# pidControllerRev8.net
KiCad netlist of a schematic drawn in EAGLE
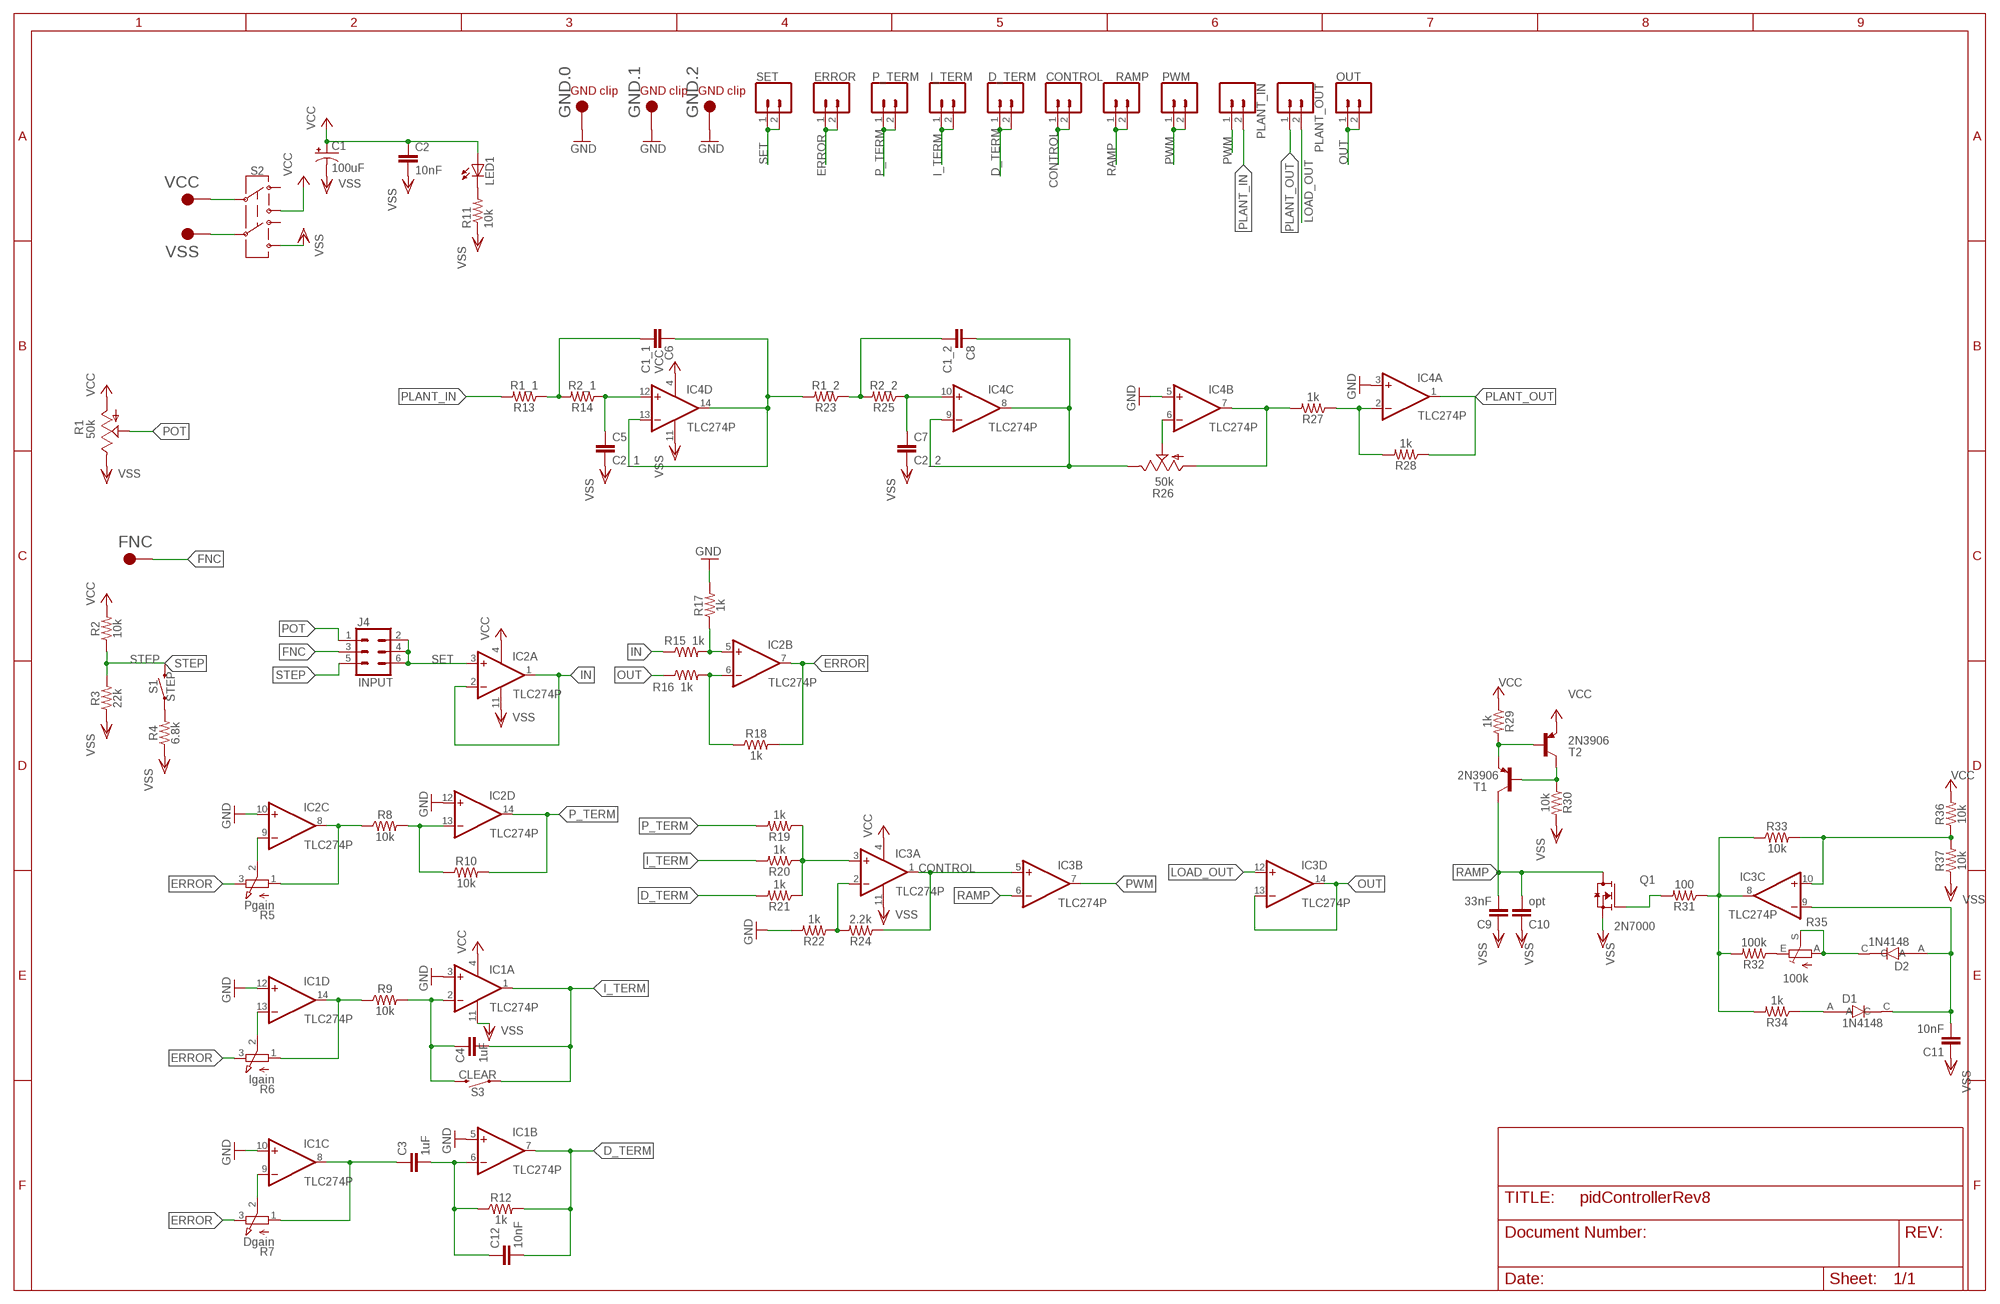
[diagram p0: schematic, sheet 1]

(export (version "E")
  (design (tool "Eeschema 10.0.6"))
  (components
    (comp (ref "C1")
      (value "100uF")
      (footprint "eagle-import:SANYO-OSCON_C")
      (libsource (lib "eagle-import") (part "CPOL-USSANYO_C"))
    )
    (comp (ref "C2")
      (value "10nF")
      (footprint "eagle-import:C1206")
      (libsource (lib "eagle-import") (part "C-EUC1206"))
    )
    (comp (ref "C3")
      (value "1uF")
      (footprint "eagle-import:C1206")
      (libsource (lib "eagle-import") (part "C-EUC1206"))
    )
    (comp (ref "C4")
      (value "1uF")
      (footprint "eagle-import:C1206")
      (libsource (lib "eagle-import") (part "C-EUC1206"))
    )
    (comp (ref "C5")
      (value "C2_1")
      (footprint "eagle-import:C1206")
      (libsource (lib "eagle-import") (part "C-EUC1206"))
    )
    (comp (ref "C6")
      (value "C1_1")
      (footprint "eagle-import:C1206")
      (libsource (lib "eagle-import") (part "C-EUC1206"))
    )
    (comp (ref "C7")
      (value "C2_2")
      (footprint "eagle-import:C1206")
      (libsource (lib "eagle-import") (part "C-EUC1206"))
    )
    (comp (ref "C8")
      (value "C1_2")
      (footprint "eagle-import:C1206")
      (libsource (lib "eagle-import") (part "C-EUC1206"))
    )
    (comp (ref "C9")
      (value "33nF")
      (footprint "eagle-import:C1206")
      (libsource (lib "eagle-import") (part "C-EUC1206"))
    )
    (comp (ref "C10")
      (value "opt")
      (footprint "eagle-import:C050-024X044")
      (libsource (lib "eagle-import") (part "C-EU050-024X044"))
    )
    (comp (ref "C11")
      (value "10nF")
      (footprint "eagle-import:C1206")
      (libsource (lib "eagle-import") (part "C-EUC1206"))
    )
    (comp (ref "C12")
      (value "10nF")
      (footprint "eagle-import:C1206")
      (libsource (lib "eagle-import") (part "C-EUC1206"))
    )
    (comp (ref "CONTROL")
      (value "CONN_02LOCK")
      (footprint "eagle-import:1X02_LOCK")
      (libsource (lib "eagle-import") (part "CONN_02LOCK"))
    )
    (comp (ref "D1")
      (value "1N4148")
      (footprint "eagle-import:SOD2513X120N")
      (fields (field (name "MANUFACTURER") "Diodes Inc."))
      (libsource (lib "eagle-import") (part "1N4148WS-7-F"))
    )
    (comp (ref "D2")
      (value "1N4148")
      (footprint "eagle-import:SOD2513X120N")
      (fields (field (name "MANUFACTURER") "Diodes Inc."))
      (libsource (lib "eagle-import") (part "1N4148WS-7-F"))
    )
    (comp (ref "D_TERM")
      (value "CONN_02LOCK")
      (footprint "eagle-import:1X02_LOCK")
      (libsource (lib "eagle-import") (part "CONN_02LOCK"))
    )
    (comp (ref "ERROR")
      (value "CONN_02LOCK")
      (footprint "eagle-import:1X02_LOCK")
      (libsource (lib "eagle-import") (part "CONN_02LOCK"))
    )
    (comp (ref "FNC")
      (value "5016")
      (footprint "eagle-import:KEYSTONE_5016")
      (fields (field (name "MANUFACTURER") "Keystone Electronics"))
      (libsource (lib "eagle-import") (part "5016"))
    )
    (comp (ref "GND.0")
      (value "5016")
      (footprint "eagle-import:KEYSTONE_5016")
      (fields (field (name "MANUFACTURER") "Keystone Electronics"))
      (libsource (lib "eagle-import") (part "5016"))
    )
    (comp (ref "GND.1")
      (value "5016")
      (footprint "eagle-import:KEYSTONE_5016")
      (fields (field (name "MANUFACTURER") "Keystone Electronics"))
      (libsource (lib "eagle-import") (part "5016"))
    )
    (comp (ref "GND.2")
      (value "5016")
      (footprint "eagle-import:KEYSTONE_5016")
      (fields (field (name "MANUFACTURER") "Keystone Electronics"))
      (libsource (lib "eagle-import") (part "5016"))
    )
    (comp (ref "IC1")
      (value "TLC274P")
      (footprint "eagle-import:DIL14")
      (libsource (lib "eagle-import") (part "TLC274P"))
    )
    (comp (ref "IC2")
      (value "TLC274P")
      (footprint "eagle-import:DIL14")
      (libsource (lib "eagle-import") (part "TLC274P"))
    )
    (comp (ref "IC3")
      (value "TLC274P")
      (footprint "eagle-import:DIL14")
      (libsource (lib "eagle-import") (part "linear_262_TLC274P"))
    )
    (comp (ref "IC4")
      (value "TLC274P")
      (footprint "eagle-import:DIL14")
      (libsource (lib "eagle-import") (part "TLC274P"))
    )
    (comp (ref "I_TERM")
      (value "CONN_02LOCK")
      (footprint "eagle-import:1X02_LOCK")
      (libsource (lib "eagle-import") (part "CONN_02LOCK"))
    )
    (comp (ref "J4")
      (value "INPUT")
      (footprint "eagle-import:2X3")
      (libsource (lib "eagle-import") (part "CONN_03X2FEMALE"))
    )
    (comp (ref "LED1")
      (value "LEDCHIPLED_1206")
      (footprint "eagle-import:CHIPLED_1206")
      (libsource (lib "eagle-import") (part "LEDCHIPLED_1206"))
    )
    (comp (ref "OUT")
      (value "CONN_02LOCK")
      (footprint "eagle-import:1X02_LOCK")
      (libsource (lib "eagle-import") (part "CONN_02LOCK"))
    )
    (comp (ref "PLANT_IN")
      (value "CONN_02LOCK")
      (footprint "eagle-import:1X02_LOCK")
      (libsource (lib "eagle-import") (part "CONN_02LOCK"))
    )
    (comp (ref "PLANT_OUT")
      (value "CONN_02LOCK")
      (footprint "eagle-import:1X02_LOCK")
      (libsource (lib "eagle-import") (part "CONN_02LOCK"))
    )
    (comp (ref "PWM")
      (value "CONN_02LOCK")
      (footprint "eagle-import:1X02_LOCK")
      (libsource (lib "eagle-import") (part "CONN_02LOCK"))
    )
    (comp (ref "P_TERM")
      (value "CONN_02LOCK")
      (footprint "eagle-import:1X02_LOCK")
      (libsource (lib "eagle-import") (part "CONN_02LOCK"))
    )
    (comp (ref "Q1")
      (value "2N7000")
      (footprint "eagle-import:TO92254P458H750-3")
      (fields (field (name "MANUFACTURER") "Diotec Semiconductor"))
      (libsource (lib "eagle-import") (part "2N7000"))
    )
    (comp (ref "R1")
      (value "50k")
      (footprint "eagle-import:B25P")
      (libsource (lib "eagle-import") (part "TRIM_US-B25P"))
    )
    (comp (ref "R2")
      (value "10k")
      (footprint "eagle-import:1206")
      (libsource (lib "eagle-import") (part "RESISTOR1206"))
    )
    (comp (ref "R3")
      (value "22k")
      (footprint "eagle-import:1206")
      (libsource (lib "eagle-import") (part "RESISTOR1206"))
    )
    (comp (ref "R4")
      (value "6.8k")
      (footprint "eagle-import:1206")
      (libsource (lib "eagle-import") (part "RESISTOR1206"))
    )
    (comp (ref "R5")
      (value "Pgain")
      (footprint "eagle-import:EVUF")
      (libsource (lib "eagle-import") (part "EVUAF2"))
    )
    (comp (ref "R6")
      (value "Igain")
      (footprint "eagle-import:EVUF")
      (libsource (lib "eagle-import") (part "EVUAF2"))
    )
    (comp (ref "R7")
      (value "Dgain")
      (footprint "eagle-import:EVUF")
      (libsource (lib "eagle-import") (part "EVUAF2"))
    )
    (comp (ref "R8")
      (value "10k")
      (footprint "eagle-import:1206")
      (libsource (lib "eagle-import") (part "RESISTOR1206"))
    )
    (comp (ref "R9")
      (value "10k")
      (footprint "eagle-import:1206")
      (libsource (lib "eagle-import") (part "RESISTOR1206"))
    )
    (comp (ref "R10")
      (value "10k")
      (footprint "eagle-import:1206")
      (libsource (lib "eagle-import") (part "RESISTOR1206"))
    )
    (comp (ref "R11")
      (value "10k")
      (footprint "eagle-import:R1206")
      (libsource (lib "eagle-import") (part "R-US_R1206"))
    )
    (comp (ref "R12")
      (value "1k")
      (footprint "eagle-import:1206")
      (libsource (lib "eagle-import") (part "RESISTOR1206"))
    )
    (comp (ref "R13")
      (value "R1_1")
      (footprint "eagle-import:1206")
      (libsource (lib "eagle-import") (part "RESISTOR1206"))
    )
    (comp (ref "R14")
      (value "R2_1")
      (footprint "eagle-import:1206")
      (libsource (lib "eagle-import") (part "RESISTOR1206"))
    )
    (comp (ref "R15")
      (value "1k")
      (footprint "eagle-import:1206")
      (libsource (lib "eagle-import") (part "RESISTOR1206"))
    )
    (comp (ref "R16")
      (value "1k")
      (footprint "eagle-import:1206")
      (libsource (lib "eagle-import") (part "RESISTOR1206"))
    )
    (comp (ref "R17")
      (value "1k")
      (footprint "eagle-import:1206")
      (libsource (lib "eagle-import") (part "RESISTOR1206"))
    )
    (comp (ref "R18")
      (value "1k")
      (footprint "eagle-import:1206")
      (libsource (lib "eagle-import") (part "RESISTOR1206"))
    )
    (comp (ref "R19")
      (value "1k")
      (footprint "eagle-import:1206")
      (libsource (lib "eagle-import") (part "RESISTOR1206"))
    )
    (comp (ref "R20")
      (value "1k")
      (footprint "eagle-import:1206")
      (libsource (lib "eagle-import") (part "RESISTOR1206"))
    )
    (comp (ref "R21")
      (value "1k")
      (footprint "eagle-import:1206")
      (libsource (lib "eagle-import") (part "RESISTOR1206"))
    )
    (comp (ref "R22")
      (value "1k")
      (footprint "eagle-import:1206")
      (libsource (lib "eagle-import") (part "RESISTOR1206"))
    )
    (comp (ref "R23")
      (value "R1_2")
      (footprint "eagle-import:1206")
      (libsource (lib "eagle-import") (part "RESISTOR1206"))
    )
    (comp (ref "R24")
      (value "2.2k")
      (footprint "eagle-import:1206")
      (libsource (lib "eagle-import") (part "RESISTOR1206"))
    )
    (comp (ref "R25")
      (value "R2_2")
      (footprint "eagle-import:1206")
      (libsource (lib "eagle-import") (part "RESISTOR1206"))
    )
    (comp (ref "R26")
      (value "50k")
      (footprint "eagle-import:B25P")
      (libsource (lib "eagle-import") (part "TRIM_US-B25P"))
    )
    (comp (ref "R27")
      (value "1k")
      (footprint "eagle-import:1206")
      (libsource (lib "eagle-import") (part "RESISTOR1206"))
    )
    (comp (ref "R28")
      (value "1k")
      (footprint "eagle-import:1206")
      (libsource (lib "eagle-import") (part "RESISTOR1206"))
    )
    (comp (ref "R29")
      (value "1k")
      (footprint "eagle-import:1206")
      (libsource (lib "eagle-import") (part "RESISTOR1206"))
    )
    (comp (ref "R30")
      (value "10k")
      (footprint "eagle-import:1206")
      (libsource (lib "eagle-import") (part "RESISTOR1206"))
    )
    (comp (ref "R31")
      (value "100")
      (footprint "eagle-import:1206")
      (libsource (lib "eagle-import") (part "RESISTOR1206"))
    )
    (comp (ref "R32")
      (value "100k")
      (footprint "eagle-import:1206")
      (libsource (lib "eagle-import") (part "RESISTOR1206"))
    )
    (comp (ref "R33")
      (value "10k")
      (footprint "eagle-import:1206")
      (libsource (lib "eagle-import") (part "RESISTOR1206"))
    )
    (comp (ref "R34")
      (value "1k")
      (footprint "eagle-import:1206")
      (libsource (lib "eagle-import") (part "RESISTOR1206"))
    )
    (comp (ref "R35")
      (value "100k")
      (footprint "eagle-import:S64W")
      (libsource (lib "eagle-import") (part "TRIM_EU-S64W"))
    )
    (comp (ref "R36")
      (value "10k")
      (footprint "eagle-import:1206")
      (libsource (lib "eagle-import") (part "RESISTOR1206"))
    )
    (comp (ref "R37")
      (value "10k")
      (footprint "eagle-import:1206")
      (libsource (lib "eagle-import") (part "RESISTOR1206"))
    )
    (comp (ref "RAMP")
      (value "CONN_02LOCK")
      (footprint "eagle-import:1X02_LOCK")
      (libsource (lib "eagle-import") (part "CONN_02LOCK"))
    )
    (comp (ref "S1")
      (value "STEP")
      (footprint "eagle-import:TACTILE_SWITCH_SMD_5.2MM")
      (libsource (lib "eagle-import") (part "MOMENTARY-SWITCH-SPST-SMD-5.2MM"))
    )
    (comp (ref "S2")
      (value "SWITCH-DPDT-SMD-AYZ0202")
      (footprint "eagle-import:SWITCH_DPDT_SMD_AYZ0202")
      (libsource (lib "eagle-import") (part "SWITCH-DPDT-SMD-AYZ0202"))
    )
    (comp (ref "S3")
      (value "CLEAR")
      (footprint "eagle-import:TACTILE_SWITCH_SMD_5.2MM")
      (libsource (lib "eagle-import") (part "MOMENTARY-SWITCH-SPST-SMD-5.2MM"))
    )
    (comp (ref "SET")
      (value "CONN_02LOCK")
      (footprint "eagle-import:1X02_LOCK")
      (libsource (lib "eagle-import") (part "CONN_02LOCK"))
    )
    (comp (ref "T1")
      (value "2N3906")
      (footprint "eagle-import:TO92-EBC")
      (libsource (lib "eagle-import") (part "-PNP-TO92-EBC2N3906"))
    )
    (comp (ref "T2")
      (value "2N3906")
      (footprint "eagle-import:TO92-EBC")
      (libsource (lib "eagle-import") (part "-PNP-TO92-EBC2N3906"))
    )
    (comp (ref "VCC")
      (value "5016")
      (footprint "eagle-import:KEYSTONE_5016")
      (fields (field (name "MANUFACTURER") "Keystone Electronics"))
      (libsource (lib "eagle-import") (part "5016"))
    )
    (comp (ref "VSS")
      (value "5016")
      (footprint "eagle-import:KEYSTONE_5016")
      (fields (field (name "MANUFACTURER") "Keystone Electronics"))
      (libsource (lib "eagle-import") (part "5016"))
    )
  )
  (nets
    (net (code "1") (name "/CONTROL") (class "Default")
      (node (ref "CONTROL") (pin "1") (pinfunction "1_1") (pintype "passive"))
      (node (ref "CONTROL") (pin "2") (pinfunction "2_2") (pintype "passive"))
      (node (ref "IC3") (pin "1") (pinfunction "OUT_1") (pintype "output"))
      (node (ref "IC3") (pin "5") (pinfunction "+IN_5") (pintype "input"))
      (node (ref "R24") (pin "1") (pinfunction "1_1") (pintype "passive"))
    )
    (net (code "2") (name "/SET") (class "Default")
      (node (ref "IC2") (pin "3") (pinfunction "+IN_3") (pintype "input"))
      (node (ref "J4") (pin "2") (pinfunction "2_2") (pintype "bidirectional"))
      (node (ref "J4") (pin "4") (pinfunction "4_4") (pintype "bidirectional"))
      (node (ref "J4") (pin "6") (pinfunction "6_6") (pintype "bidirectional"))
      (node (ref "SET") (pin "1") (pinfunction "1_1") (pintype "passive"))
      (node (ref "SET") (pin "2") (pinfunction "2_2") (pintype "passive"))
    )
    (net (code "3") (name "D_TERM") (class "Default")
      (node (ref "C12") (pin "2") (pinfunction "2_2") (pintype "passive"))
      (node (ref "D_TERM") (pin "1") (pinfunction "1_1") (pintype "passive"))
      (node (ref "D_TERM") (pin "2") (pinfunction "2_2") (pintype "passive"))
      (node (ref "IC1") (pin "7") (pinfunction "OUT_7") (pintype "output"))
      (node (ref "R12") (pin "2") (pinfunction "2_2") (pintype "passive"))
      (node (ref "R21") (pin "2") (pinfunction "2_2") (pintype "passive"))
    )
    (net (code "4") (name "ERROR") (class "Default")
      (node (ref "ERROR") (pin "1") (pinfunction "1_1") (pintype "passive"))
      (node (ref "ERROR") (pin "2") (pinfunction "2_2") (pintype "passive"))
      (node (ref "IC2") (pin "7") (pinfunction "OUT_7") (pintype "output"))
      (node (ref "R18") (pin "2") (pinfunction "2_2") (pintype "passive"))
      (node (ref "R5") (pin "3") (pinfunction "E_3") (pintype "passive"))
      (node (ref "R6") (pin "3") (pinfunction "E_3") (pintype "passive"))
      (node (ref "R7") (pin "3") (pinfunction "E_3") (pintype "passive"))
    )
    (net (code "5") (name "FNC") (class "Default")
      (node (ref "FNC") (pin "TP") (pinfunction "TP_TP") (pintype "passive"))
      (node (ref "J4") (pin "3") (pinfunction "3_3") (pintype "bidirectional"))
    )
    (net (code "6") (name "GND") (class "Default")
      (node (ref "GND.0") (pin "TP") (pinfunction "TP_TP") (pintype "passive"))
      (node (ref "GND.1") (pin "TP") (pinfunction "TP_TP") (pintype "passive"))
      (node (ref "GND.2") (pin "TP") (pinfunction "TP_TP") (pintype "passive"))
      (node (ref "IC1") (pin "10") (pinfunction "+IN_10") (pintype "input"))
      (node (ref "IC1") (pin "12") (pinfunction "+IN_12") (pintype "input"))
      (node (ref "IC1") (pin "3") (pinfunction "+IN_3") (pintype "input"))
      (node (ref "IC1") (pin "5") (pinfunction "+IN_5") (pintype "input"))
      (node (ref "IC2") (pin "10") (pinfunction "+IN_10") (pintype "input"))
      (node (ref "IC2") (pin "12") (pinfunction "+IN_12") (pintype "input"))
      (node (ref "IC4") (pin "3") (pinfunction "+IN_3") (pintype "input"))
      (node (ref "IC4") (pin "5") (pinfunction "+IN_5") (pintype "input"))
      (node (ref "R17") (pin "2") (pinfunction "2_2") (pintype "passive"))
      (node (ref "R22") (pin "2") (pinfunction "2_2") (pintype "passive"))
    )
    (net (code "7") (name "IN") (class "Default")
      (node (ref "IC2") (pin "1") (pinfunction "OUT_1") (pintype "output"))
      (node (ref "IC2") (pin "2") (pinfunction "-IN_2") (pintype "input"))
      (node (ref "R15") (pin "1") (pinfunction "1_1") (pintype "passive"))
    )
    (net (code "8") (name "I_TERM") (class "Default")
      (node (ref "C4") (pin "2") (pinfunction "2_2") (pintype "passive"))
      (node (ref "IC1") (pin "1") (pinfunction "OUT_1") (pintype "output"))
      (node (ref "I_TERM") (pin "1") (pinfunction "1_1") (pintype "passive"))
      (node (ref "I_TERM") (pin "2") (pinfunction "2_2") (pintype "passive"))
      (node (ref "R20") (pin "2") (pinfunction "2_2") (pintype "passive"))
      (node (ref "S3") (pin "1") (pinfunction "1_1") (pintype "passive"))
    )
    (net (code "9") (name "LOAD_OUT") (class "Default")
      (node (ref "IC3") (pin "12") (pinfunction "+IN_12") (pintype "input"))
      (node (ref "PLANT_OUT") (pin "2") (pinfunction "2_2") (pintype "passive"))
    )
    (net (code "10") (name "Net-(C6-Pad2)") (class "Default")
      (node (ref "C6") (pin "2") (pinfunction "2_2") (pintype "passive"))
      (node (ref "R13") (pin "1") (pinfunction "1_1") (pintype "passive"))
      (node (ref "R14") (pin "2") (pinfunction "2_2") (pintype "passive"))
    )
    (net (code "11") (name "Net-(C8-Pad2)") (class "Default")
      (node (ref "C8") (pin "2") (pinfunction "2_2") (pintype "passive"))
      (node (ref "R23") (pin "1") (pinfunction "1_1") (pintype "passive"))
      (node (ref "R25") (pin "2") (pinfunction "2_2") (pintype "passive"))
    )
    (net (code "12") (name "Net-(D1-PadA)") (class "Default")
      (node (ref "D1") (pin "A") (pinfunction "A_A") (pintype "passive"))
      (node (ref "R34") (pin "1") (pinfunction "1_1") (pintype "passive"))
    )
    (net (code "13") (name "Net-(D2-PadC)") (class "Default")
      (node (ref "D2") (pin "C") (pinfunction "C_C") (pintype "passive"))
      (node (ref "R35") (pin "A") (pinfunction "A_A") (pintype "passive"))
      (node (ref "R35") (pin "S") (pinfunction "S_S") (pintype "passive"))
    )
    (net (code "14") (name "Net-(IC1A--IN)") (class "Default")
      (node (ref "C4") (pin "1") (pinfunction "1_1") (pintype "passive"))
      (node (ref "IC1") (pin "2") (pinfunction "-IN_2") (pintype "input"))
      (node (ref "R9") (pin "2") (pinfunction "2_2") (pintype "passive"))
      (node (ref "S3") (pin "3") (pinfunction "2_3") (pintype "passive"))
    )
    (net (code "15") (name "Net-(IC1B--IN)") (class "Default")
      (node (ref "C12") (pin "1") (pinfunction "1_1") (pintype "passive"))
      (node (ref "C3") (pin "2") (pinfunction "2_2") (pintype "passive"))
      (node (ref "IC1") (pin "6") (pinfunction "-IN_6") (pintype "input"))
      (node (ref "R12") (pin "1") (pinfunction "1_1") (pintype "passive"))
    )
    (net (code "16") (name "Net-(IC1C--IN)") (class "Default")
      (node (ref "IC1") (pin "9") (pinfunction "-IN_9") (pintype "input"))
      (node (ref "R7") (pin "2") (pinfunction "S_2") (pintype "passive"))
    )
    (net (code "17") (name "Net-(IC1C-OUT)") (class "Default")
      (node (ref "C3") (pin "1") (pinfunction "1_1") (pintype "passive"))
      (node (ref "IC1") (pin "8") (pinfunction "OUT_8") (pintype "output"))
      (node (ref "R7") (pin "1") (pinfunction "A_1") (pintype "passive"))
    )
    (net (code "18") (name "Net-(IC1D--IN)") (class "Default")
      (node (ref "IC1") (pin "13") (pinfunction "-IN_13") (pintype "input"))
      (node (ref "R6") (pin "2") (pinfunction "S_2") (pintype "passive"))
    )
    (net (code "19") (name "Net-(IC1D-OUT)") (class "Default")
      (node (ref "IC1") (pin "14") (pinfunction "OUT_14") (pintype "output"))
      (node (ref "R6") (pin "1") (pinfunction "A_1") (pintype "passive"))
      (node (ref "R9") (pin "1") (pinfunction "1_1") (pintype "passive"))
    )
    (net (code "20") (name "Net-(IC2B-+IN)") (class "Default")
      (node (ref "IC2") (pin "5") (pinfunction "+IN_5") (pintype "input"))
      (node (ref "R15") (pin "2") (pinfunction "2_2") (pintype "passive"))
      (node (ref "R17") (pin "1") (pinfunction "1_1") (pintype "passive"))
    )
    (net (code "21") (name "Net-(IC2B--IN)") (class "Default")
      (node (ref "IC2") (pin "6") (pinfunction "-IN_6") (pintype "input"))
      (node (ref "R16") (pin "2") (pinfunction "2_2") (pintype "passive"))
      (node (ref "R18") (pin "1") (pinfunction "1_1") (pintype "passive"))
    )
    (net (code "22") (name "Net-(IC2C--IN)") (class "Default")
      (node (ref "IC2") (pin "9") (pinfunction "-IN_9") (pintype "input"))
      (node (ref "R5") (pin "2") (pinfunction "S_2") (pintype "passive"))
    )
    (net (code "23") (name "Net-(IC2C-OUT)") (class "Default")
      (node (ref "IC2") (pin "8") (pinfunction "OUT_8") (pintype "output"))
      (node (ref "R5") (pin "1") (pinfunction "A_1") (pintype "passive"))
      (node (ref "R8") (pin "1") (pinfunction "1_1") (pintype "passive"))
    )
    (net (code "24") (name "Net-(IC2D--IN)") (class "Default")
      (node (ref "IC2") (pin "13") (pinfunction "-IN_13") (pintype "input"))
      (node (ref "R10") (pin "1") (pinfunction "1_1") (pintype "passive"))
      (node (ref "R8") (pin "2") (pinfunction "2_2") (pintype "passive"))
    )
    (net (code "25") (name "Net-(IC3A-+IN)") (class "Default")
      (node (ref "IC3") (pin "3") (pinfunction "+IN_3") (pintype "input"))
      (node (ref "R19") (pin "1") (pinfunction "1_1") (pintype "passive"))
      (node (ref "R20") (pin "1") (pinfunction "1_1") (pintype "passive"))
      (node (ref "R21") (pin "1") (pinfunction "1_1") (pintype "passive"))
    )
    (net (code "26") (name "Net-(IC3A--IN)") (class "Default")
      (node (ref "IC3") (pin "2") (pinfunction "-IN_2") (pintype "input"))
      (node (ref "R22") (pin "1") (pinfunction "1_1") (pintype "passive"))
      (node (ref "R24") (pin "2") (pinfunction "2_2") (pintype "passive"))
    )
    (net (code "27") (name "Net-(IC3C-+IN)") (class "Default")
      (node (ref "IC3") (pin "10") (pinfunction "+IN_10") (pintype "input"))
      (node (ref "R33") (pin "2") (pinfunction "2_2") (pintype "passive"))
      (node (ref "R36") (pin "1") (pinfunction "1_1") (pintype "passive"))
      (node (ref "R37") (pin "2") (pinfunction "2_2") (pintype "passive"))
    )
    (net (code "28") (name "Net-(IC3C--IN)") (class "Default")
      (node (ref "C11") (pin "2") (pinfunction "2_2") (pintype "passive"))
      (node (ref "D1") (pin "C") (pinfunction "C_C") (pintype "passive"))
      (node (ref "D2") (pin "A") (pinfunction "A_A") (pintype "passive"))
      (node (ref "IC3") (pin "9") (pinfunction "-IN_9") (pintype "input"))
    )
    (net (code "29") (name "Net-(IC3C-OUT)") (class "Default")
      (node (ref "IC3") (pin "8") (pinfunction "OUT_8") (pintype "output"))
      (node (ref "R31") (pin "1") (pinfunction "1_1") (pintype "passive"))
      (node (ref "R32") (pin "2") (pinfunction "2_2") (pintype "passive"))
      (node (ref "R33") (pin "1") (pinfunction "1_1") (pintype "passive"))
      (node (ref "R34") (pin "2") (pinfunction "2_2") (pintype "passive"))
    )
    (net (code "30") (name "Net-(IC4A--IN)") (class "Default")
      (node (ref "IC4") (pin "2") (pinfunction "-IN_2") (pintype "input"))
      (node (ref "R27") (pin "1") (pinfunction "1_1") (pintype "passive"))
      (node (ref "R28") (pin "2") (pinfunction "2_2") (pintype "passive"))
    )
    (net (code "31") (name "Net-(IC4B--IN)") (class "Default")
      (node (ref "IC4") (pin "6") (pinfunction "-IN_6") (pintype "input"))
      (node (ref "R26") (pin "S") (pinfunction "S_S") (pintype "passive"))
    )
    (net (code "32") (name "Net-(IC4B-OUT)") (class "Default")
      (node (ref "IC4") (pin "7") (pinfunction "OUT_7") (pintype "output"))
      (node (ref "R26") (pin "A") (pinfunction "A_A") (pintype "passive"))
      (node (ref "R27") (pin "2") (pinfunction "2_2") (pintype "passive"))
    )
    (net (code "33") (name "Net-(IC4C-+IN)") (class "Default")
      (node (ref "C7") (pin "1") (pinfunction "1_1") (pintype "passive"))
      (node (ref "IC4") (pin "10") (pinfunction "+IN_10") (pintype "input"))
      (node (ref "R25") (pin "1") (pinfunction "1_1") (pintype "passive"))
    )
    (net (code "34") (name "Net-(IC4C--IN)") (class "Default")
      (node (ref "C8") (pin "1") (pinfunction "1_1") (pintype "passive"))
      (node (ref "IC4") (pin "8") (pinfunction "OUT_8") (pintype "output"))
      (node (ref "IC4") (pin "9") (pinfunction "-IN_9") (pintype "input"))
      (node (ref "R26") (pin "E") (pinfunction "E_E") (pintype "passive"))
    )
    (net (code "35") (name "Net-(IC4D-+IN)") (class "Default")
      (node (ref "C5") (pin "1") (pinfunction "1_1") (pintype "passive"))
      (node (ref "IC4") (pin "12") (pinfunction "+IN_12") (pintype "input"))
      (node (ref "R14") (pin "1") (pinfunction "1_1") (pintype "passive"))
    )
    (net (code "36") (name "Net-(IC4D--IN)") (class "Default")
      (node (ref "C6") (pin "1") (pinfunction "1_1") (pintype "passive"))
      (node (ref "IC4") (pin "13") (pinfunction "-IN_13") (pintype "input"))
      (node (ref "IC4") (pin "14") (pinfunction "OUT_14") (pintype "output"))
      (node (ref "R23") (pin "2") (pinfunction "2_2") (pintype "passive"))
    )
    (net (code "37") (name "Net-(LED1-PadC)") (class "Default")
      (node (ref "LED1") (pin "C") (pinfunction "C_C") (pintype "passive"))
      (node (ref "R11") (pin "2") (pinfunction "2_2") (pintype "passive"))
    )
    (net (code "38") (name "Net-(Q1-G)") (class "Default")
      (node (ref "Q1") (pin "2") (pinfunction "G_2") (pintype "passive"))
      (node (ref "R31") (pin "2") (pinfunction "2_2") (pintype "passive"))
    )
    (net (code "39") (name "Net-(R4-Pad2)") (class "Default")
      (node (ref "R4") (pin "2") (pinfunction "2_2") (pintype "passive"))
      (node (ref "S1") (pin "1") (pinfunction "1_1") (pintype "passive"))
    )
    (net (code "40") (name "Net-(R29-Pad2)") (class "Default")
      (node (ref "R29") (pin "2") (pinfunction "2_2") (pintype "passive"))
      (node (ref "T1") (pin "E") (pinfunction "E_E") (pintype "passive"))
      (node (ref "T2") (pin "B") (pinfunction "B_B") (pintype "passive"))
    )
    (net (code "41") (name "Net-(R30-Pad1)") (class "Default")
      (node (ref "R30") (pin "1") (pinfunction "1_1") (pintype "passive"))
      (node (ref "T1") (pin "B") (pinfunction "B_B") (pintype "passive"))
      (node (ref "T2") (pin "C") (pinfunction "C_C") (pintype "passive"))
    )
    (net (code "42") (name "Net-(R32-Pad1)") (class "Default")
      (node (ref "R32") (pin "1") (pinfunction "1_1") (pintype "passive"))
      (node (ref "R35") (pin "E") (pinfunction "E_E") (pintype "passive"))
    )
    (net (code "43") (name "Net-(S2-Pad2)") (class "Default")
      (node (ref "S2") (pin "2") (pinfunction "2_2") (pintype "bidirectional"))
      (node (ref "VCC") (pin "TP") (pinfunction "TP_TP") (pintype "passive"))
    )
    (net (code "44") (name "Net-(S2-Pad5)") (class "Default")
      (node (ref "S2") (pin "5") (pinfunction "5_5") (pintype "bidirectional"))
      (node (ref "VSS") (pin "TP") (pinfunction "TP_TP") (pintype "passive"))
    )
    (net (code "45") (name "OUT") (class "Default")
      (node (ref "IC3") (pin "13") (pinfunction "-IN_13") (pintype "input"))
      (node (ref "IC3") (pin "14") (pinfunction "OUT_14") (pintype "output"))
      (node (ref "OUT") (pin "1") (pinfunction "1_1") (pintype "passive"))
      (node (ref "OUT") (pin "2") (pinfunction "2_2") (pintype "passive"))
      (node (ref "R16") (pin "1") (pinfunction "1_1") (pintype "passive"))
    )
    (net (code "46") (name "PLANT_IN") (class "Default")
      (node (ref "PLANT_IN") (pin "2") (pinfunction "2_2") (pintype "passive"))
      (node (ref "R13") (pin "2") (pinfunction "2_2") (pintype "passive"))
    )
    (net (code "47") (name "PLANT_OUT") (class "Default")
      (node (ref "IC4") (pin "1") (pinfunction "OUT_1") (pintype "output"))
      (node (ref "PLANT_OUT") (pin "1") (pinfunction "1_1") (pintype "passive"))
      (node (ref "R28") (pin "1") (pinfunction "1_1") (pintype "passive"))
    )
    (net (code "48") (name "POT") (class "Default")
      (node (ref "J4") (pin "1") (pinfunction "1_1") (pintype "bidirectional"))
      (node (ref "R1") (pin "S") (pinfunction "S_S") (pintype "passive"))
    )
    (net (code "49") (name "PWM") (class "Default")
      (node (ref "IC3") (pin "7") (pinfunction "OUT_7") (pintype "output"))
      (node (ref "PLANT_IN") (pin "1") (pinfunction "1_1") (pintype "passive"))
      (node (ref "PWM") (pin "1") (pinfunction "1_1") (pintype "passive"))
      (node (ref "PWM") (pin "2") (pinfunction "2_2") (pintype "passive"))
    )
    (net (code "50") (name "P_TERM") (class "Default")
      (node (ref "IC2") (pin "14") (pinfunction "OUT_14") (pintype "output"))
      (node (ref "P_TERM") (pin "1") (pinfunction "1_1") (pintype "passive"))
      (node (ref "P_TERM") (pin "2") (pinfunction "2_2") (pintype "passive"))
      (node (ref "R10") (pin "2") (pinfunction "2_2") (pintype "passive"))
      (node (ref "R19") (pin "2") (pinfunction "2_2") (pintype "passive"))
    )
    (net (code "51") (name "RAMP") (class "Default")
      (node (ref "C10") (pin "2") (pinfunction "2_2") (pintype "passive"))
      (node (ref "C9") (pin "2") (pinfunction "2_2") (pintype "passive"))
      (node (ref "IC3") (pin "6") (pinfunction "-IN_6") (pintype "input"))
      (node (ref "Q1") (pin "3") (pinfunction "D_3") (pintype "passive"))
      (node (ref "RAMP") (pin "1") (pinfunction "1_1") (pintype "passive"))
      (node (ref "RAMP") (pin "2") (pinfunction "2_2") (pintype "passive"))
      (node (ref "T1") (pin "C") (pinfunction "C_C") (pintype "passive"))
    )
    (net (code "52") (name "STEP") (class "Default")
      (node (ref "J4") (pin "5") (pinfunction "5_5") (pintype "bidirectional"))
      (node (ref "R2") (pin "1") (pinfunction "1_1") (pintype "passive"))
      (node (ref "R3") (pin "2") (pinfunction "2_2") (pintype "passive"))
      (node (ref "S1") (pin "3") (pinfunction "2_3") (pintype "passive"))
    )
    (net (code "53") (name "VCC") (class "Default")
      (node (ref "C1") (pin "+") (pinfunction "+_+") (pintype "passive"))
      (node (ref "C2") (pin "1") (pinfunction "1_1") (pintype "passive"))
      (node (ref "IC1") (pin "4") (pinfunction "V+_4") (pintype "power_in"))
      (node (ref "IC2") (pin "4") (pinfunction "V+_4") (pintype "power_in"))
      (node (ref "IC3") (pin "4") (pinfunction "V+_4") (pintype "power_in"))
      (node (ref "IC4") (pin "4") (pinfunction "V+_4") (pintype "power_in"))
      (node (ref "LED1") (pin "A") (pinfunction "A_A") (pintype "passive"))
      (node (ref "R1") (pin "A") (pinfunction "A_A") (pintype "passive"))
      (node (ref "R2") (pin "2") (pinfunction "2_2") (pintype "passive"))
      (node (ref "R29") (pin "1") (pinfunction "1_1") (pintype "passive"))
      (node (ref "R36") (pin "2") (pinfunction "2_2") (pintype "passive"))
      (node (ref "S2") (pin "3") (pinfunction "3_3") (pintype "bidirectional"))
      (node (ref "T2") (pin "E") (pinfunction "E_E") (pintype "passive"))
    )
    (net (code "54") (name "VSS") (class "Default")
      (node (ref "C1") (pin "-") (pinfunction "-_-") (pintype "passive"))
      (node (ref "C10") (pin "1") (pinfunction "1_1") (pintype "passive"))
      (node (ref "C11") (pin "1") (pinfunction "1_1") (pintype "passive"))
      (node (ref "C2") (pin "2") (pinfunction "2_2") (pintype "passive"))
      (node (ref "C5") (pin "2") (pinfunction "2_2") (pintype "passive"))
      (node (ref "C7") (pin "2") (pinfunction "2_2") (pintype "passive"))
      (node (ref "C9") (pin "1") (pinfunction "1_1") (pintype "passive"))
      (node (ref "IC1") (pin "11") (pinfunction "V-_11") (pintype "power_in"))
      (node (ref "IC2") (pin "11") (pinfunction "V-_11") (pintype "power_in"))
      (node (ref "IC3") (pin "11") (pinfunction "V-_11") (pintype "power_in"))
      (node (ref "IC4") (pin "11") (pinfunction "V-_11") (pintype "power_in"))
      (node (ref "Q1") (pin "1") (pinfunction "S_1") (pintype "passive"))
      (node (ref "R1") (pin "E") (pinfunction "E_E") (pintype "passive"))
      (node (ref "R11") (pin "1") (pinfunction "1_1") (pintype "passive"))
      (node (ref "R3") (pin "1") (pinfunction "1_1") (pintype "passive"))
      (node (ref "R30") (pin "2") (pinfunction "2_2") (pintype "passive"))
      (node (ref "R37") (pin "1") (pinfunction "1_1") (pintype "passive"))
      (node (ref "R4") (pin "1") (pinfunction "1_1") (pintype "passive"))
      (node (ref "S2") (pin "6") (pinfunction "6_6") (pintype "bidirectional"))
    )
    (net (code "55") (name "unconnected-(S2-Pad1)") (class "Default")
      (node (ref "S2") (pin "1") (pinfunction "1_1") (pintype "bidirectional"))
    )
    (net (code "56") (name "unconnected-(S2-Pad4)") (class "Default")
      (node (ref "S2") (pin "4") (pinfunction "4_4") (pintype "bidirectional"))
    )
  )
)
